# Detector.net
KiCad netlist of a schematic drawn in Altium Designer
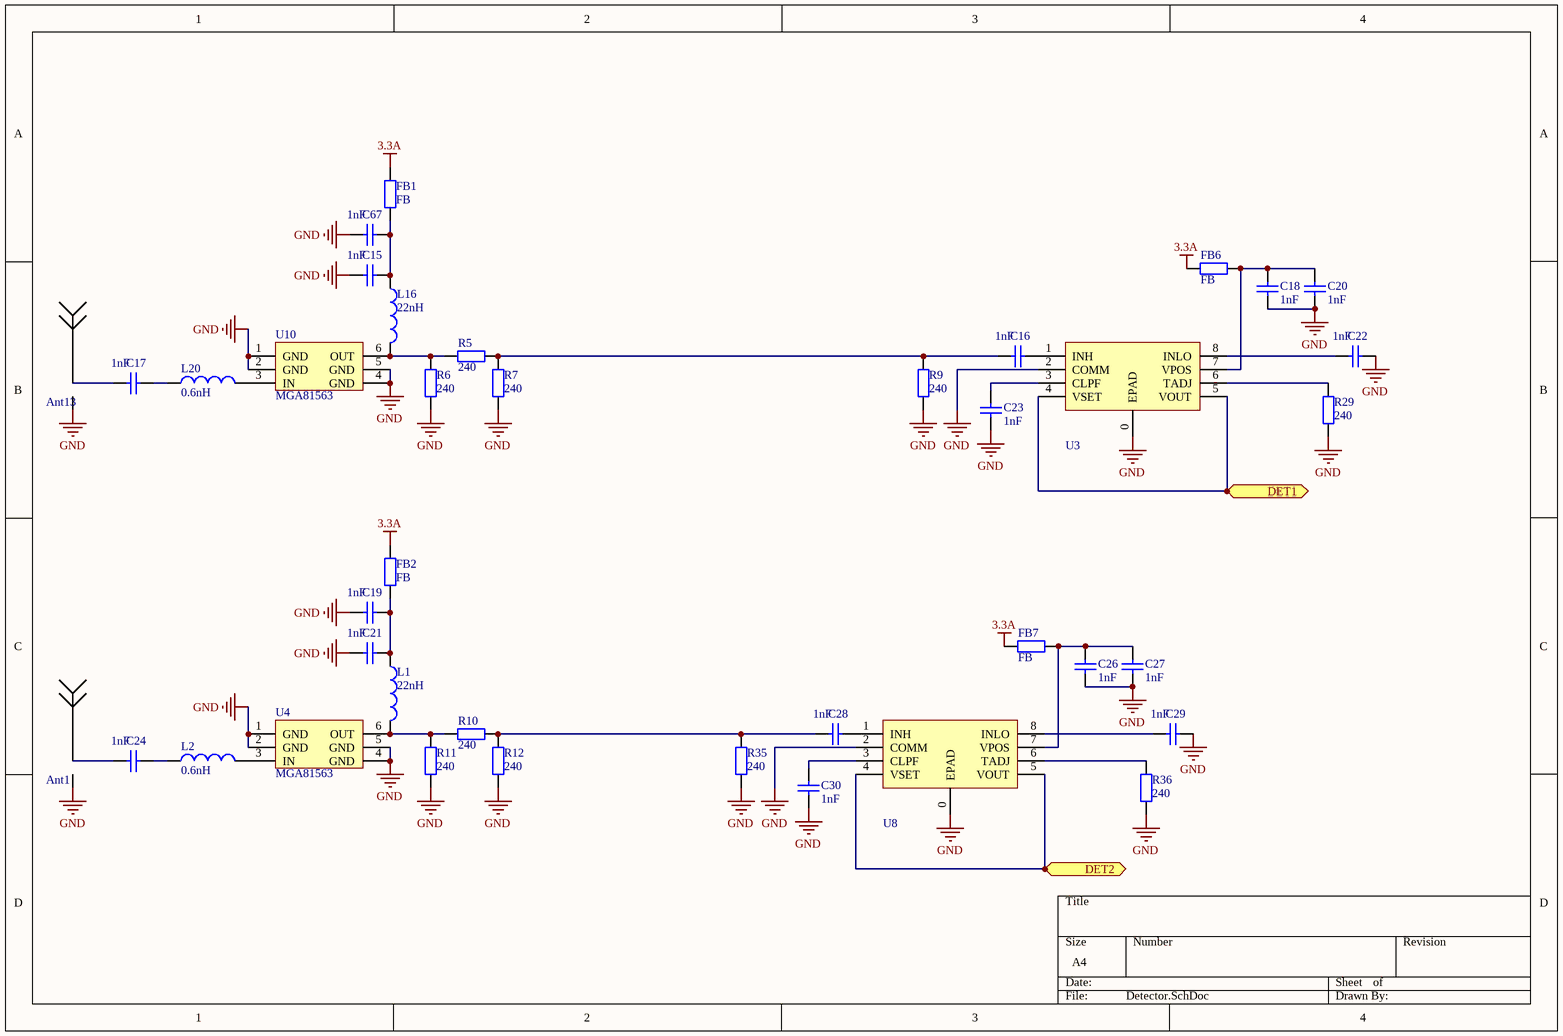
[diagram p0: Detector.SchDoc]

(export (version "E")
  (design (tool "Eeschema 10.0.6"))
  (components
    (comp (ref "Ant1") (value "Antenna") (footprint "SMA-2") (libsource (lib "F4SDR") (part "Antenna")))
    (comp (ref "Ant13") (value "Antenna") (footprint "SMA-2") (libsource (lib "F4SDR") (part "Antenna")))
    (comp (ref "C15")
      (value "1nF")
      (footprint "0402")
      (description "Capacitor")
      (fields (field (name "PUBLISHER") "Altium Limited"))
      (libsource (lib "RTC6705") (part "Cap"))
    )
    (comp (ref "C16")
      (value "1nF")
      (footprint "0402")
      (description "Capacitor")
      (fields (field (name "PUBLISHER") "Altium Limited"))
      (libsource (lib "RTC6705") (part "Cap"))
    )
    (comp (ref "C17")
      (value "1nF")
      (footprint "0402")
      (description "Capacitor")
      (fields (field (name "PUBLISHER") "Altium Limited"))
      (libsource (lib "RTC6705") (part "Cap"))
    )
    (comp (ref "C18")
      (value "1nF")
      (footprint "0402")
      (description "Capacitor")
      (fields (field (name "PUBLISHER") "Altium Limited"))
      (libsource (lib "RTC6705") (part "Cap"))
    )
    (comp (ref "C19")
      (value "1nF")
      (footprint "0402")
      (description "Capacitor")
      (fields (field (name "PUBLISHER") "Altium Limited"))
      (libsource (lib "RTC6705") (part "Cap"))
    )
    (comp (ref "C20")
      (value "1nF")
      (footprint "0402")
      (description "Capacitor")
      (fields (field (name "PUBLISHER") "Altium Limited"))
      (libsource (lib "RTC6705") (part "Cap"))
    )
    (comp (ref "C21")
      (value "1nF")
      (footprint "0402")
      (description "Capacitor")
      (fields (field (name "PUBLISHER") "Altium Limited"))
      (libsource (lib "RTC6705") (part "Cap"))
    )
    (comp (ref "C22")
      (value "1nF")
      (footprint "0402")
      (description "Capacitor")
      (fields (field (name "PUBLISHER") "Altium Limited"))
      (libsource (lib "RTC6705") (part "Cap"))
    )
    (comp (ref "C23")
      (value "1nF")
      (footprint "0402")
      (description "Capacitor")
      (fields (field (name "PUBLISHER") "Altium Limited"))
      (libsource (lib "RTC6705") (part "Cap"))
    )
    (comp (ref "C24")
      (value "1nF")
      (footprint "0402")
      (description "Capacitor")
      (fields (field (name "PUBLISHER") "Altium Limited"))
      (libsource (lib "RTC6705") (part "Cap"))
    )
    (comp (ref "C26")
      (value "1nF")
      (footprint "0402")
      (description "Capacitor")
      (fields (field (name "PUBLISHER") "Altium Limited"))
      (libsource (lib "RTC6705") (part "Cap"))
    )
    (comp (ref "C27")
      (value "1nF")
      (footprint "0402")
      (description "Capacitor")
      (fields (field (name "PUBLISHER") "Altium Limited"))
      (libsource (lib "RTC6705") (part "Cap"))
    )
    (comp (ref "C28")
      (value "1nF")
      (footprint "0402")
      (description "Capacitor")
      (fields (field (name "PUBLISHER") "Altium Limited"))
      (libsource (lib "RTC6705") (part "Cap"))
    )
    (comp (ref "C29")
      (value "1nF")
      (footprint "0402")
      (description "Capacitor")
      (fields (field (name "PUBLISHER") "Altium Limited"))
      (libsource (lib "RTC6705") (part "Cap"))
    )
    (comp (ref "C30")
      (value "1nF")
      (footprint "0402")
      (description "Capacitor")
      (fields (field (name "PUBLISHER") "Altium Limited"))
      (libsource (lib "RTC6705") (part "Cap"))
    )
    (comp (ref "C67")
      (value "1nF")
      (footprint "0402")
      (description "Capacitor")
      (fields (field (name "PUBLISHER") "Altium Limited"))
      (libsource (lib "RTC6705") (part "Cap"))
    )
    (comp (ref "FB1")
      (value "FB")
      (footprint "0402")
      (description "Resistor")
      (fields (field (name "PUBLISHER") "Altium Limited"))
      (libsource (lib "Miscellaneous Devices") (part "Res2"))
    )
    (comp (ref "FB2")
      (value "FB")
      (footprint "0402")
      (description "Resistor")
      (fields (field (name "PUBLISHER") "Altium Limited"))
      (libsource (lib "Miscellaneous Devices") (part "Res2"))
    )
    (comp (ref "FB6")
      (value "FB")
      (footprint "0402")
      (description "Resistor")
      (fields (field (name "PUBLISHER") "Altium Limited"))
      (libsource (lib "") (part "Res2_1"))
    )
    (comp (ref "FB7")
      (value "FB")
      (footprint "0402")
      (description "Resistor")
      (fields (field (name "PUBLISHER") "Altium Limited"))
      (libsource (lib "") (part "Res2_1"))
    )
    (comp (ref "L1")
      (value "22nH")
      (footprint "0402")
      (description "Inductor")
      (fields (field (name "PUBLISHER") "Altium Limited"))
      (libsource (lib "Miscellaneous Devices") (part "Inductor"))
    )
    (comp (ref "L2")
      (value "0.6nH")
      (footprint "0402")
      (description "Inductor")
      (fields (field (name "PUBLISHER") "Altium Limited"))
      (libsource (lib "Miscellaneous Devices") (part "Inductor"))
    )
    (comp (ref "L16")
      (value "22nH")
      (footprint "0402")
      (description "Inductor")
      (fields (field (name "PUBLISHER") "Altium Limited"))
      (libsource (lib "Miscellaneous Devices") (part "Inductor"))
    )
    (comp (ref "L20")
      (value "0.6nH")
      (footprint "0402")
      (description "Inductor")
      (fields (field (name "PUBLISHER") "Altium Limited"))
      (libsource (lib "Miscellaneous Devices") (part "Inductor"))
    )
    (comp (ref "R5")
      (value "240")
      (footprint "0402")
      (description "Resistor")
      (fields (field (name "PUBLISHER") "Altium Limited"))
      (libsource (lib "") (part "Res2_1"))
    )
    (comp (ref "R6")
      (value "240")
      (footprint "0402")
      (description "Resistor")
      (fields (field (name "PUBLISHER") "Altium Limited"))
      (libsource (lib "Miscellaneous Devices") (part "Res2"))
    )
    (comp (ref "R7")
      (value "240")
      (footprint "0402")
      (description "Resistor")
      (fields (field (name "PUBLISHER") "Altium Limited"))
      (libsource (lib "Miscellaneous Devices") (part "Res2"))
    )
    (comp (ref "R9")
      (value "240")
      (footprint "0402")
      (description "Resistor")
      (fields (field (name "PUBLISHER") "Altium Limited"))
      (libsource (lib "Miscellaneous Devices") (part "Res2"))
    )
    (comp (ref "R10")
      (value "240")
      (footprint "0402")
      (description "Resistor")
      (fields (field (name "PUBLISHER") "Altium Limited"))
      (libsource (lib "") (part "Res2_1"))
    )
    (comp (ref "R11")
      (value "240")
      (footprint "0402")
      (description "Resistor")
      (fields (field (name "PUBLISHER") "Altium Limited"))
      (libsource (lib "Miscellaneous Devices") (part "Res2"))
    )
    (comp (ref "R12")
      (value "240")
      (footprint "0402")
      (description "Resistor")
      (fields (field (name "PUBLISHER") "Altium Limited"))
      (libsource (lib "Miscellaneous Devices") (part "Res2"))
    )
    (comp (ref "R29")
      (value "240")
      (footprint "0402")
      (description "Resistor")
      (fields (field (name "PUBLISHER") "Altium Limited"))
      (libsource (lib "Miscellaneous Devices") (part "Res2"))
    )
    (comp (ref "R35")
      (value "240")
      (footprint "0402")
      (description "Resistor")
      (fields (field (name "PUBLISHER") "Altium Limited"))
      (libsource (lib "Miscellaneous Devices") (part "Res2"))
    )
    (comp (ref "R36")
      (value "240")
      (footprint "0402")
      (description "Resistor")
      (fields (field (name "PUBLISHER") "Altium Limited"))
      (libsource (lib "Miscellaneous Devices") (part "Res2"))
    )
    (comp (ref "U3") (value "AD8319") (footprint "AD8319") (libsource (lib "F4SDR") (part "AD8319")))
    (comp (ref "U4") (value "MGA81563") (footprint "SC-70-6") (libsource (lib "F4SDR") (part "MGA81563")))
    (comp (ref "U8") (value "AD8319") (footprint "AD8319") (libsource (lib "F4SDR") (part "AD8319")))
    (comp (ref "U10") (value "MGA81563") (footprint "SC-70-6") (libsource (lib "F4SDR") (part "MGA81563")))
  )
  (nets
    (net (code "1") (name "/DET1") (class "Default")
      (node (ref "U3") (pin "4") (pinfunction "VSET_4") (pintype "passive"))
      (node (ref "U3") (pin "5") (pinfunction "VOUT_5") (pintype "passive"))
    )
    (net (code "2") (name "/DET2") (class "Default")
      (node (ref "U8") (pin "4") (pinfunction "VSET_4") (pintype "passive"))
      (node (ref "U8") (pin "5") (pinfunction "VOUT_5") (pintype "passive"))
    )
    (net (code "3") (name "3.3A") (class "Default")
      (node (ref "FB1") (pin "1") (pinfunction "1_1") (pintype "passive"))
      (node (ref "FB2") (pin "1") (pinfunction "1_1") (pintype "passive"))
      (node (ref "FB6") (pin "1") (pinfunction "1_1") (pintype "passive"))
      (node (ref "FB7") (pin "1") (pinfunction "1_1") (pintype "passive"))
    )
    (net (code "4") (name "GND") (class "Default")
      (node (ref "Ant1") (pin "GND") (pinfunction "G_GND") (pintype "passive"))
      (node (ref "Ant13") (pin "GND") (pinfunction "G_GND") (pintype "passive"))
      (node (ref "C15") (pin "1") (pinfunction "1_1") (pintype "passive"))
      (node (ref "C18") (pin "1") (pinfunction "1_1") (pintype "passive"))
      (node (ref "C19") (pin "1") (pinfunction "1_1") (pintype "passive"))
      (node (ref "C20") (pin "1") (pinfunction "1_1") (pintype "passive"))
      (node (ref "C21") (pin "1") (pinfunction "1_1") (pintype "passive"))
      (node (ref "C22") (pin "2") (pinfunction "2_2") (pintype "passive"))
      (node (ref "C23") (pin "1") (pinfunction "1_1") (pintype "passive"))
      (node (ref "C26") (pin "1") (pinfunction "1_1") (pintype "passive"))
      (node (ref "C27") (pin "1") (pinfunction "1_1") (pintype "passive"))
      (node (ref "C29") (pin "2") (pinfunction "2_2") (pintype "passive"))
      (node (ref "C30") (pin "1") (pinfunction "1_1") (pintype "passive"))
      (node (ref "C67") (pin "1") (pinfunction "1_1") (pintype "passive"))
      (node (ref "R11") (pin "2") (pinfunction "2_2") (pintype "passive"))
      (node (ref "R12") (pin "2") (pinfunction "2_2") (pintype "passive"))
      (node (ref "R29") (pin "2") (pinfunction "2_2") (pintype "passive"))
      (node (ref "R35") (pin "2") (pinfunction "2_2") (pintype "passive"))
      (node (ref "R36") (pin "2") (pinfunction "2_2") (pintype "passive"))
      (node (ref "R6") (pin "2") (pinfunction "2_2") (pintype "passive"))
      (node (ref "R7") (pin "2") (pinfunction "2_2") (pintype "passive"))
      (node (ref "R9") (pin "2") (pinfunction "2_2") (pintype "passive"))
      (node (ref "U10") (pin "1") (pinfunction "GND_1") (pintype "passive"))
      (node (ref "U10") (pin "2") (pinfunction "GND_2") (pintype "passive"))
      (node (ref "U10") (pin "4") (pinfunction "GND_4") (pintype "passive"))
      (node (ref "U10") (pin "5") (pinfunction "GND_5") (pintype "passive"))
      (node (ref "U3") (pin "0") (pinfunction "EPAD_0") (pintype "passive"))
      (node (ref "U3") (pin "2") (pinfunction "COMM_2") (pintype "passive"))
      (node (ref "U4") (pin "1") (pinfunction "GND_1") (pintype "passive"))
      (node (ref "U4") (pin "2") (pinfunction "GND_2") (pintype "passive"))
      (node (ref "U4") (pin "4") (pinfunction "GND_4") (pintype "passive"))
      (node (ref "U4") (pin "5") (pinfunction "GND_5") (pintype "passive"))
      (node (ref "U8") (pin "0") (pinfunction "EPAD_0") (pintype "passive"))
      (node (ref "U8") (pin "2") (pinfunction "COMM_2") (pintype "passive"))
    )
    (net (code "5") (name "Net-(Ant1-Pad1)") (class "Default")
      (node (ref "Ant1") (pin "1") (pinfunction "1_1") (pintype "passive"))
      (node (ref "C24") (pin "1") (pinfunction "1_1") (pintype "passive"))
    )
    (net (code "6") (name "Net-(Ant13-Pad1)") (class "Default")
      (node (ref "Ant13") (pin "1") (pinfunction "1_1") (pintype "passive"))
      (node (ref "C17") (pin "1") (pinfunction "1_1") (pintype "passive"))
    )
    (net (code "7") (name "Net-(C15-Pad2)") (class "Default")
      (node (ref "C15") (pin "2") (pinfunction "2_2") (pintype "passive"))
      (node (ref "C67") (pin "2") (pinfunction "2_2") (pintype "passive"))
      (node (ref "FB1") (pin "2") (pinfunction "2_2") (pintype "passive"))
      (node (ref "L16") (pin "1") (pinfunction "1_1") (pintype "passive"))
    )
    (net (code "8") (name "Net-(C16-Pad1)") (class "Default")
      (node (ref "C16") (pin "1") (pinfunction "1_1") (pintype "passive"))
      (node (ref "R5") (pin "2") (pinfunction "2_2") (pintype "passive"))
      (node (ref "R7") (pin "1") (pinfunction "1_1") (pintype "passive"))
      (node (ref "R9") (pin "1") (pinfunction "1_1") (pintype "passive"))
    )
    (net (code "9") (name "Net-(C17-Pad2)") (class "Default")
      (node (ref "C17") (pin "2") (pinfunction "2_2") (pintype "passive"))
      (node (ref "L20") (pin "1") (pinfunction "1_1") (pintype "passive"))
    )
    (net (code "10") (name "Net-(C19-Pad2)") (class "Default")
      (node (ref "C19") (pin "2") (pinfunction "2_2") (pintype "passive"))
      (node (ref "C21") (pin "2") (pinfunction "2_2") (pintype "passive"))
      (node (ref "FB2") (pin "2") (pinfunction "2_2") (pintype "passive"))
      (node (ref "L1") (pin "1") (pinfunction "1_1") (pintype "passive"))
    )
    (net (code "11") (name "Net-(C24-Pad2)") (class "Default")
      (node (ref "C24") (pin "2") (pinfunction "2_2") (pintype "passive"))
      (node (ref "L2") (pin "1") (pinfunction "1_1") (pintype "passive"))
    )
    (net (code "12") (name "Net-(C28-Pad1)") (class "Default")
      (node (ref "C28") (pin "1") (pinfunction "1_1") (pintype "passive"))
      (node (ref "R10") (pin "2") (pinfunction "2_2") (pintype "passive"))
      (node (ref "R12") (pin "1") (pinfunction "1_1") (pintype "passive"))
      (node (ref "R35") (pin "1") (pinfunction "1_1") (pintype "passive"))
    )
    (net (code "13") (name "Net-(U3-CLPF)") (class "Default")
      (node (ref "C23") (pin "2") (pinfunction "2_2") (pintype "passive"))
      (node (ref "U3") (pin "3") (pinfunction "CLPF_3") (pintype "passive"))
    )
    (net (code "14") (name "Net-(U3-INH)") (class "Default")
      (node (ref "C16") (pin "2") (pinfunction "2_2") (pintype "passive"))
      (node (ref "U3") (pin "1") (pinfunction "INH_1") (pintype "passive"))
    )
    (net (code "15") (name "Net-(U3-INLO)") (class "Default")
      (node (ref "C22") (pin "1") (pinfunction "1_1") (pintype "passive"))
      (node (ref "U3") (pin "8") (pinfunction "INLO_8") (pintype "passive"))
    )
    (net (code "16") (name "Net-(U3-TADJ)") (class "Default")
      (node (ref "R29") (pin "1") (pinfunction "1_1") (pintype "passive"))
      (node (ref "U3") (pin "6") (pinfunction "TADJ_6") (pintype "passive"))
    )
    (net (code "17") (name "Net-(U3-VPOS)") (class "Default")
      (node (ref "C18") (pin "2") (pinfunction "2_2") (pintype "passive"))
      (node (ref "C20") (pin "2") (pinfunction "2_2") (pintype "passive"))
      (node (ref "FB6") (pin "2") (pinfunction "2_2") (pintype "passive"))
      (node (ref "U3") (pin "7") (pinfunction "VPOS_7") (pintype "passive"))
    )
    (net (code "18") (name "Net-(U4-IN)") (class "Default")
      (node (ref "L2") (pin "2") (pinfunction "2_2") (pintype "passive"))
      (node (ref "U4") (pin "3") (pinfunction "IN_3") (pintype "passive"))
    )
    (net (code "19") (name "Net-(U4-OUT)") (class "Default")
      (node (ref "L1") (pin "2") (pinfunction "2_2") (pintype "passive"))
      (node (ref "R10") (pin "1") (pinfunction "1_1") (pintype "passive"))
      (node (ref "R11") (pin "1") (pinfunction "1_1") (pintype "passive"))
      (node (ref "U4") (pin "6") (pinfunction "OUT_6") (pintype "passive"))
    )
    (net (code "20") (name "Net-(U8-CLPF)") (class "Default")
      (node (ref "C30") (pin "2") (pinfunction "2_2") (pintype "passive"))
      (node (ref "U8") (pin "3") (pinfunction "CLPF_3") (pintype "passive"))
    )
    (net (code "21") (name "Net-(U8-INH)") (class "Default")
      (node (ref "C28") (pin "2") (pinfunction "2_2") (pintype "passive"))
      (node (ref "U8") (pin "1") (pinfunction "INH_1") (pintype "passive"))
    )
    (net (code "22") (name "Net-(U8-INLO)") (class "Default")
      (node (ref "C29") (pin "1") (pinfunction "1_1") (pintype "passive"))
      (node (ref "U8") (pin "8") (pinfunction "INLO_8") (pintype "passive"))
    )
    (net (code "23") (name "Net-(U8-TADJ)") (class "Default")
      (node (ref "R36") (pin "1") (pinfunction "1_1") (pintype "passive"))
      (node (ref "U8") (pin "6") (pinfunction "TADJ_6") (pintype "passive"))
    )
    (net (code "24") (name "Net-(U8-VPOS)") (class "Default")
      (node (ref "C26") (pin "2") (pinfunction "2_2") (pintype "passive"))
      (node (ref "C27") (pin "2") (pinfunction "2_2") (pintype "passive"))
      (node (ref "FB7") (pin "2") (pinfunction "2_2") (pintype "passive"))
      (node (ref "U8") (pin "7") (pinfunction "VPOS_7") (pintype "passive"))
    )
    (net (code "25") (name "Net-(U10-IN)") (class "Default")
      (node (ref "L20") (pin "2") (pinfunction "2_2") (pintype "passive"))
      (node (ref "U10") (pin "3") (pinfunction "IN_3") (pintype "passive"))
    )
    (net (code "26") (name "Net-(U10-OUT)") (class "Default")
      (node (ref "L16") (pin "2") (pinfunction "2_2") (pintype "passive"))
      (node (ref "R5") (pin "1") (pinfunction "1_1") (pintype "passive"))
      (node (ref "R6") (pin "1") (pinfunction "1_1") (pintype "passive"))
      (node (ref "U10") (pin "6") (pinfunction "OUT_6") (pintype "passive"))
    )
  )
)
